# LED_Blink_v8.net
KiCad netlist of a schematic drawn in EAGLE
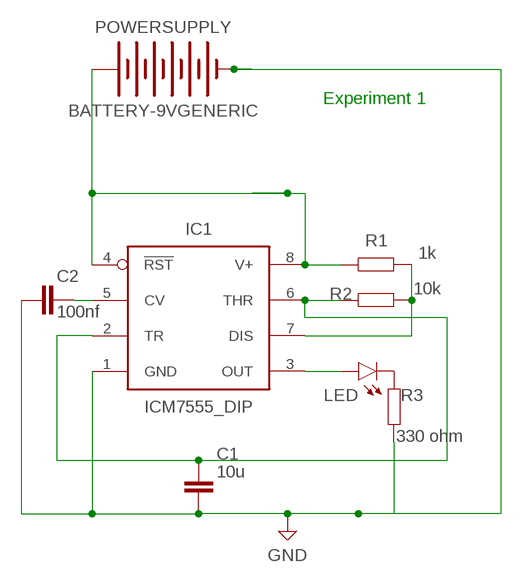
[diagram p0: schematic, sheet 1]

(export (version "E")
  (design (tool "Eeschema 10.0.6"))
  (components
    (comp (ref "C1")
      (value "10u")
      (footprint "eagle-import:CAPC1005X60")
      (libsource (lib "eagle-import") (part "CCHIP-0402(1005-METRIC)_"))
    )
    (comp (ref "C2")
      (value "100nf")
      (footprint "eagle-import:CAPC1005X60")
      (libsource (lib "eagle-import") (part "CCHIP-0402(1005-METRIC)_"))
    )
    (comp (ref "IC1")
      (value "ICM7555_DIP")
      (footprint "eagle-import:DIP826W53P254L959H508Q8B")
      (fields
        (field (name "MANUFACTURER") "Renesas Electronics Corporation")
        (field (name "MPN") "ICM7555IPAZ")
      )
      (libsource (lib "eagle-import") (part "555_DIPICM7"))
    )
    (comp (ref "LED")
      (value "CHIP-FLAT-B_0603-0.35MM")
      (footprint "eagle-import:LEDC1608X35N_FLAT-B")
      (libsource (lib "eagle-import") (part "CHIP-FLAT-B_0603-0.35MM"))
    )
    (comp (ref "POWERSUPPLY")
      (value "BATTERY-9VGENERIC")
      (footprint "eagle-import:BATTERY-GENERIC")
      (libsource (lib "eagle-import") (part "BATTERY-9VGENERIC"))
    )
    (comp (ref "R1")
      (value "1k")
      (footprint "eagle-import:RESC1005X40")
      (libsource (lib "eagle-import") (part "RCHIP-0402(1005-METRIC)_"))
    )
    (comp (ref "R2")
      (value "10k")
      (footprint "eagle-import:RESC1005X40")
      (libsource (lib "eagle-import") (part "RCHIP-0402(1005-METRIC)_"))
    )
    (comp (ref "R3")
      (value "330 ohm")
      (footprint "eagle-import:RESC1005X40")
      (libsource (lib "eagle-import") (part "RCHIP-0402(1005-METRIC)_"))
    )
  )
  (nets
    (net (code "1") (name "GND") (class "Default")
      (node (ref "C1") (pin "2") (pinfunction "2_2") (pintype "passive"))
      (node (ref "C2") (pin "2") (pinfunction "2_2") (pintype "passive"))
      (node (ref "IC1") (pin "1") (pinfunction "GND_1") (pintype "power_in"))
      (node (ref "POWERSUPPLY") (pin "-") (pinfunction "-_-") (pintype "passive"))
      (node (ref "R3") (pin "1") (pinfunction "1_1") (pintype "passive"))
    )
    (net (code "2") (name "Net-(IC1-CV)") (class "Default")
      (node (ref "C2") (pin "1") (pinfunction "1_1") (pintype "passive"))
      (node (ref "IC1") (pin "5") (pinfunction "CV_5") (pintype "input"))
    )
    (net (code "3") (name "Net-(IC1-DIS)") (class "Default")
      (node (ref "IC1") (pin "7") (pinfunction "DIS_7") (pintype "input"))
      (node (ref "R1") (pin "2") (pinfunction "2_2") (pintype "passive"))
      (node (ref "R2") (pin "2") (pinfunction "2_2") (pintype "passive"))
    )
    (net (code "4") (name "Net-(IC1-OUT)") (class "Default")
      (node (ref "IC1") (pin "3") (pinfunction "OUT_3") (pintype "output"))
      (node (ref "LED") (pin "A") (pinfunction "A_A") (pintype "passive"))
    )
    (net (code "5") (name "Net-(IC1-THR)") (class "Default")
      (node (ref "C1") (pin "1") (pinfunction "1_1") (pintype "passive"))
      (node (ref "IC1") (pin "2") (pinfunction "TR_2") (pintype "input"))
      (node (ref "IC1") (pin "6") (pinfunction "THR_6") (pintype "input"))
      (node (ref "R2") (pin "1") (pinfunction "1_1") (pintype "passive"))
    )
    (net (code "6") (name "Net-(IC1-V+)") (class "Default")
      (node (ref "IC1") (pin "4") (pinfunction "~{RST}_4") (pintype "input"))
      (node (ref "IC1") (pin "8") (pinfunction "V+_8") (pintype "power_in"))
      (node (ref "POWERSUPPLY") (pin "+") (pinfunction "+_+") (pintype "passive"))
      (node (ref "R1") (pin "1") (pinfunction "1_1") (pintype "passive"))
    )
    (net (code "7") (name "Net-(LED-PadC)") (class "Default")
      (node (ref "LED") (pin "C") (pinfunction "C_C") (pintype "passive"))
      (node (ref "R3") (pin "2") (pinfunction "2_2") (pintype "passive"))
    )
  )
)
